# DroneMCU.net
KiCad netlist of a schematic drawn in Altium Designer
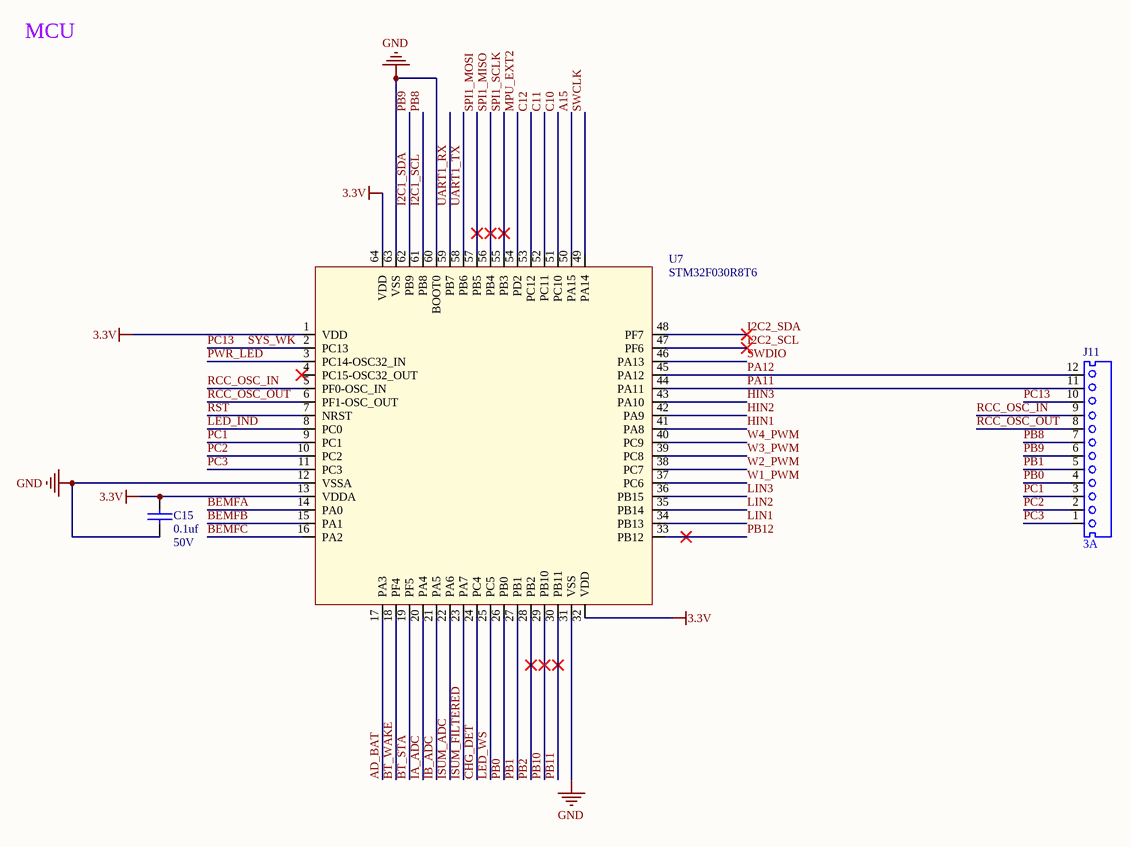
[diagram p0: DroneMCU.SchDoc]

(export (version "E")
  (design (tool "Eeschema 10.0.6"))
  (components
    (comp (ref "C15")
      (value "0.1uf")
      (footprint "CAPC0603-RW")
      (description "GP CHIP CAP 0.015uF 50V 10% 0603 TYPE X7R")
      (fields
        (field (name "TOLERANCE") "10%")
        (field (name "VOLTAGE") "50V")
        (field (name "Comment") "PXL456470-1530")
      )
      (libsource (lib "P-Capacitors") (part "CAP0603 0.015uF 50V 10%"))
    )
    (comp (ref "J11")
      (value "T690300029300")
      (footprint "CONN 12P PH=2.5 ST HAA250A-12A")
      (description "CONNECTOR 12 PIN P:2.5MM P2.54-12 K")
      (fields
        (field (name "MFG") "金科基")
        (field (name "MFG PART") "HAA250A-12A")
        (field (name "CURRENT") "3A")
        (field (name "CREATE_NAME") "Nathan")
      )
      (libsource (lib "C-Connector") (part "CONN 12P PH=2.5 ST HAA250A-12A"))
    )
    (comp (ref "U7")
      (value "T610300097225")
      (footprint "QFP50P1200X1200X160-64N")
      (description "MCU STM32F030RCT6TR LQFP64 ST K")
      (fields
        (field (name "MFG") "ST     (STM意法半導體)")
        (field (name "MFG PART") "STM32F030R8T6")
        (field (name "CREATE_NAME") "Nathan")
      )
      (libsource (lib "R-Semiconductors") (part "STM32F030RCT6TR"))
    )
  )
  (nets
    (net (code "1") (name "/A15") (class "Default")
      (node (ref "U7") (pin "50") (pinfunction "PA15_50") (pintype "passive"))
    )
    (net (code "2") (name "/AD_BAT") (class "Default")
      (node (ref "U7") (pin "17") (pinfunction "PA3_17") (pintype "passive"))
    )
    (net (code "3") (name "/BEMFA") (class "Default")
      (node (ref "U7") (pin "14") (pinfunction "PA0_14") (pintype "passive"))
    )
    (net (code "4") (name "/BEMFB") (class "Default")
      (node (ref "U7") (pin "15") (pinfunction "PA1_15") (pintype "passive"))
    )
    (net (code "5") (name "/BEMFC") (class "Default")
      (node (ref "U7") (pin "16") (pinfunction "PA2_16") (pintype "passive"))
    )
    (net (code "6") (name "/BT_STA") (class "Default")
      (node (ref "U7") (pin "19") (pinfunction "PF5_19") (pintype "passive"))
    )
    (net (code "7") (name "/BT_WAKE") (class "Default")
      (node (ref "U7") (pin "18") (pinfunction "PF4_18") (pintype "passive"))
    )
    (net (code "8") (name "/C10") (class "Default")
      (node (ref "U7") (pin "51") (pinfunction "PC10_51") (pintype "passive"))
    )
    (net (code "9") (name "/C11") (class "Default")
      (node (ref "U7") (pin "52") (pinfunction "PC11_52") (pintype "passive"))
    )
    (net (code "10") (name "/C12") (class "Default")
      (node (ref "U7") (pin "53") (pinfunction "PC12_53") (pintype "passive"))
    )
    (net (code "11") (name "/CHG_DET") (class "Default")
      (node (ref "U7") (pin "24") (pinfunction "PC4_24") (pintype "passive"))
    )
    (net (code "12") (name "/HIN1") (class "Default")
      (node (ref "U7") (pin "41") (pinfunction "PA8_41") (pintype "passive"))
    )
    (net (code "13") (name "/HIN2") (class "Default")
      (node (ref "U7") (pin "42") (pinfunction "PA9_42") (pintype "passive"))
    )
    (net (code "14") (name "/HIN3") (class "Default")
      (node (ref "U7") (pin "43") (pinfunction "PA10_43") (pintype "passive"))
    )
    (net (code "15") (name "/I2C1_SCL") (class "Default")
      (node (ref "J11") (pin "7") (pinfunction "7_7") (pintype "passive"))
      (node (ref "U7") (pin "61") (pinfunction "PB8_61") (pintype "passive"))
    )
    (net (code "16") (name "/I2C1_SDA") (class "Default")
      (node (ref "J11") (pin "6") (pinfunction "6_6") (pintype "passive"))
      (node (ref "U7") (pin "62") (pinfunction "PB9_62") (pintype "passive"))
    )
    (net (code "17") (name "/I2C2_SCL") (class "Default")
      (node (ref "U7") (pin "47") (pinfunction "PF6_47") (pintype "passive+no_connect"))
    )
    (net (code "18") (name "/I2C2_SDA") (class "Default")
      (node (ref "U7") (pin "48") (pinfunction "PF7_48") (pintype "passive+no_connect"))
    )
    (net (code "19") (name "/IA_ADC") (class "Default")
      (node (ref "U7") (pin "20") (pinfunction "PA4_20") (pintype "passive"))
    )
    (net (code "20") (name "/IB_ADC") (class "Default")
      (node (ref "U7") (pin "21") (pinfunction "PA5_21") (pintype "passive"))
    )
    (net (code "21") (name "/ISUM_ADC") (class "Default")
      (node (ref "U7") (pin "22") (pinfunction "PA6_22") (pintype "passive"))
    )
    (net (code "22") (name "/ISUM_FILTERED") (class "Default")
      (node (ref "U7") (pin "23") (pinfunction "PA7_23") (pintype "passive"))
    )
    (net (code "23") (name "/LED_IND") (class "Default")
      (node (ref "U7") (pin "8") (pinfunction "PC0_8") (pintype "passive"))
    )
    (net (code "24") (name "/LED_WS") (class "Default")
      (node (ref "U7") (pin "25") (pinfunction "PC5_25") (pintype "passive"))
    )
    (net (code "25") (name "/LIN1") (class "Default")
      (node (ref "U7") (pin "34") (pinfunction "PB13_34") (pintype "passive"))
    )
    (net (code "26") (name "/LIN2") (class "Default")
      (node (ref "U7") (pin "35") (pinfunction "PB14_35") (pintype "passive"))
    )
    (net (code "27") (name "/LIN3") (class "Default")
      (node (ref "U7") (pin "36") (pinfunction "PB15_36") (pintype "passive"))
    )
    (net (code "28") (name "/MPU_EXT2") (class "Default")
      (node (ref "U7") (pin "54") (pinfunction "PD2_54") (pintype "passive"))
    )
    (net (code "29") (name "/PA11") (class "Default")
      (node (ref "J11") (pin "11") (pinfunction "11_11") (pintype "passive"))
      (node (ref "U7") (pin "44") (pinfunction "PA11_44") (pintype "passive"))
    )
    (net (code "30") (name "/PA12") (class "Default")
      (node (ref "J11") (pin "12") (pinfunction "12_12") (pintype "passive"))
      (node (ref "U7") (pin "45") (pinfunction "PA12_45") (pintype "passive"))
    )
    (net (code "31") (name "/PB0") (class "Default")
      (node (ref "J11") (pin "4") (pinfunction "4_4") (pintype "passive"))
      (node (ref "U7") (pin "26") (pinfunction "PB0_26") (pintype "passive"))
    )
    (net (code "32") (name "/PB1") (class "Default")
      (node (ref "J11") (pin "5") (pinfunction "5_5") (pintype "passive"))
      (node (ref "U7") (pin "27") (pinfunction "PB1_27") (pintype "passive"))
    )
    (net (code "33") (name "/PB2") (class "Default")
      (node (ref "U7") (pin "28") (pinfunction "PB2_28") (pintype "passive"))
    )
    (net (code "34") (name "/PB10") (class "Default")
      (node (ref "U7") (pin "29") (pinfunction "PB10_29") (pintype "passive"))
    )
    (net (code "35") (name "/PB11") (class "Default")
      (node (ref "U7") (pin "30") (pinfunction "PB11_30") (pintype "passive"))
    )
    (net (code "36") (name "/PB12") (class "Default")
      (node (ref "U7") (pin "33") (pinfunction "PB12_33") (pintype "passive"))
    )
    (net (code "37") (name "/PC1") (class "Default")
      (node (ref "J11") (pin "3") (pinfunction "3_3") (pintype "passive"))
      (node (ref "U7") (pin "9") (pinfunction "PC1_9") (pintype "passive"))
    )
    (net (code "38") (name "/PC2") (class "Default")
      (node (ref "J11") (pin "2") (pinfunction "2_2") (pintype "passive"))
      (node (ref "U7") (pin "10") (pinfunction "PC2_10") (pintype "passive"))
    )
    (net (code "39") (name "/PC3") (class "Default")
      (node (ref "J11") (pin "1") (pinfunction "1_1") (pintype "passive"))
      (node (ref "U7") (pin "11") (pinfunction "PC3_11") (pintype "passive"))
    )
    (net (code "40") (name "/PC13") (class "Default")
      (node (ref "J11") (pin "10") (pinfunction "10_10") (pintype "passive"))
      (node (ref "U7") (pin "2") (pinfunction "PC13_2") (pintype "passive"))
    )
    (net (code "41") (name "/PWR_LED") (class "Default")
      (node (ref "U7") (pin "3") (pinfunction "PC14-OSC32_IN_3") (pintype "passive"))
    )
    (net (code "42") (name "/RCC_OSC_IN") (class "Default")
      (node (ref "J11") (pin "9") (pinfunction "9_9") (pintype "passive"))
      (node (ref "U7") (pin "5") (pinfunction "PF0-OSC_IN_5") (pintype "passive"))
    )
    (net (code "43") (name "/RCC_OSC_OUT") (class "Default")
      (node (ref "J11") (pin "8") (pinfunction "8_8") (pintype "passive"))
      (node (ref "U7") (pin "6") (pinfunction "PF1-OSC_OUT_6") (pintype "passive"))
    )
    (net (code "44") (name "/RST") (class "Default")
      (node (ref "U7") (pin "7") (pinfunction "NRST_7") (pintype "passive"))
    )
    (net (code "45") (name "/SPI1_MISO") (class "Default")
      (node (ref "U7") (pin "56") (pinfunction "PB4_56") (pintype "passive"))
    )
    (net (code "46") (name "/SPI1_MOSI") (class "Default")
      (node (ref "U7") (pin "57") (pinfunction "PB5_57") (pintype "passive"))
    )
    (net (code "47") (name "/SPI1_SCLK") (class "Default")
      (node (ref "U7") (pin "55") (pinfunction "PB3_55") (pintype "passive"))
    )
    (net (code "48") (name "/SWCLK") (class "Default")
      (node (ref "U7") (pin "49") (pinfunction "PA14_49") (pintype "passive"))
    )
    (net (code "49") (name "/SWDIO") (class "Default")
      (node (ref "U7") (pin "46") (pinfunction "PA13_46") (pintype "passive"))
    )
    (net (code "50") (name "/UART1_RX") (class "Default")
      (node (ref "U7") (pin "59") (pinfunction "PB7_59") (pintype "passive"))
    )
    (net (code "51") (name "/UART1_TX") (class "Default")
      (node (ref "U7") (pin "58") (pinfunction "PB6_58") (pintype "passive"))
    )
    (net (code "52") (name "/W1_PWM") (class "Default")
      (node (ref "U7") (pin "37") (pinfunction "PC6_37") (pintype "passive"))
    )
    (net (code "53") (name "/W2_PWM") (class "Default")
      (node (ref "U7") (pin "38") (pinfunction "PC7_38") (pintype "passive"))
    )
    (net (code "54") (name "/W3_PWM") (class "Default")
      (node (ref "U7") (pin "39") (pinfunction "PC8_39") (pintype "passive"))
    )
    (net (code "55") (name "/W4_PWM") (class "Default")
      (node (ref "U7") (pin "40") (pinfunction "PC9_40") (pintype "passive"))
    )
    (net (code "56") (name "3.3V") (class "Default")
      (node (ref "C15") (pin "2") (pinfunction "2_2") (pintype "passive"))
      (node (ref "U7") (pin "1") (pinfunction "VDD_1") (pintype "passive"))
      (node (ref "U7") (pin "13") (pinfunction "VDDA_13") (pintype "passive"))
      (node (ref "U7") (pin "32") (pinfunction "VDD_32") (pintype "passive"))
      (node (ref "U7") (pin "64") (pinfunction "VDD_64") (pintype "passive"))
    )
    (net (code "57") (name "GND") (class "Default")
      (node (ref "C15") (pin "1") (pinfunction "1_1") (pintype "passive"))
      (node (ref "U7") (pin "12") (pinfunction "VSSA_12") (pintype "passive"))
      (node (ref "U7") (pin "31") (pinfunction "VSS_31") (pintype "passive"))
      (node (ref "U7") (pin "60") (pinfunction "BOOT0_60") (pintype "passive"))
      (node (ref "U7") (pin "63") (pinfunction "VSS_63") (pintype "passive"))
    )
    (net (code "58") (name "unconnected-(U7-PC15-OSC32_OUT-Pad4)") (class "Default")
      (node (ref "U7") (pin "4") (pinfunction "PC15-OSC32_OUT_4") (pintype "passive+no_connect"))
    )
  )
)
